# Peripheral.net
KiCad netlist of a schematic drawn in Altium Designer
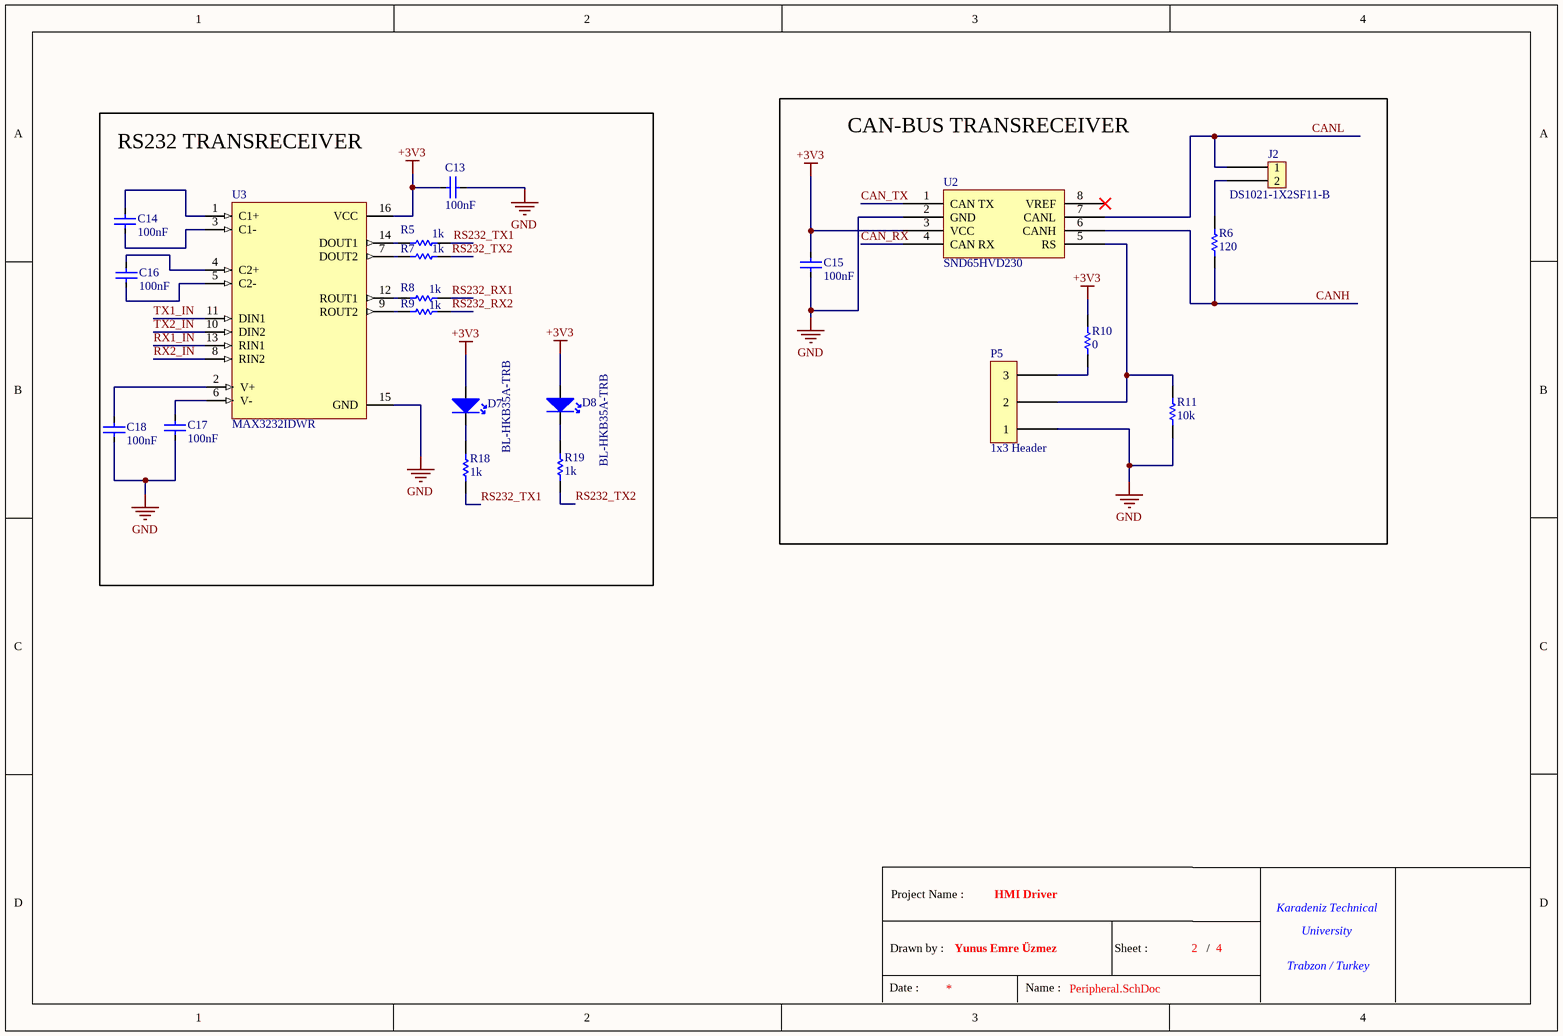
[diagram p0: Peripheral.SchDoc]

(export (version "E")
  (design (tool "Eeschema 10.0.6"))
  (components
    (comp (ref "C13")
      (value "100nF")
      (footprint "CAP-0603")
      (fields
        (field (name "MANUFACTURER") "TDK")
        (field (name "VOLTAGE") "50V")
        (field (name "TOLERANCE") "%10")
      )
      (libsource (lib "Motor_Driver") (part "CGA3E2X7R1H104K080AA"))
    )
    (comp (ref "C14")
      (value "100nF")
      (footprint "CAP-0603")
      (fields
        (field (name "MANUFACTURER") "TDK")
        (field (name "VOLTAGE") "50V")
        (field (name "TOLERANCE") "%10")
      )
      (libsource (lib "Motor_Driver") (part "CGA3E2X7R1H104K080AA"))
    )
    (comp (ref "C15")
      (value "100nF")
      (footprint "CAP-0603")
      (fields
        (field (name "MANUFACTURER") "TDK")
        (field (name "VOLTAGE") "50V")
        (field (name "TOLERANCE") "%10")
      )
      (libsource (lib "Motor_Driver") (part "CGA3E2X7R1H104K080AA"))
    )
    (comp (ref "C16")
      (value "100nF")
      (footprint "CAP-0603")
      (fields
        (field (name "MANUFACTURER") "TDK")
        (field (name "VOLTAGE") "50V")
        (field (name "TOLERANCE") "%10")
      )
      (libsource (lib "Motor_Driver") (part "CGA3E2X7R1H104K080AA"))
    )
    (comp (ref "C17")
      (value "100nF")
      (footprint "CAP-0603")
      (fields
        (field (name "MANUFACTURER") "TDK")
        (field (name "VOLTAGE") "50V")
        (field (name "TOLERANCE") "%10")
      )
      (libsource (lib "Motor_Driver") (part "CGA3E2X7R1H104K080AA"))
    )
    (comp (ref "C18")
      (value "100nF")
      (footprint "CAP-0603")
      (fields
        (field (name "MANUFACTURER") "TDK")
        (field (name "VOLTAGE") "50V")
        (field (name "TOLERANCE") "%10")
      )
      (libsource (lib "Motor_Driver") (part "CGA3E2X7R1H104K080AA"))
    )
    (comp (ref "D7")
      (value "BL-HKB35A-TRB")
      (footprint "LED-0805")
      (fields (field (name "MANUFACTURER") "BRIGHT LED"))
      (libsource (lib "Motor_Driver") (part "BL-HKB35A-TRB"))
    )
    (comp (ref "D8")
      (value "BL-HKB35A-TRB")
      (footprint "LED-0805")
      (fields (field (name "MANUFACTURER") "BRIGHT LED"))
      (libsource (lib "Motor_Driver") (part "BL-HKB35A-TRB"))
    )
    (comp (ref "J2")
      (value "DS1021-1X2SF11-B")
      (footprint "1x2 HEADER")
      (fields (field (name "MANUFACTURER") "KLS Electronic"))
      (libsource (lib "jl_lib") (part "DS1021-1X2SF11-B"))
    )
    (comp (ref "P5")
      (value "1x3 Header")
      (footprint "1x3 Header (2.54 mm)")
      (libsource (lib "LoRatoUSB") (part "1x3 Header"))
    )
    (comp (ref "R5")
      (value "1k")
      (footprint "Motor_Driver:RES-0603")
      (fields
        (field (name "MANUFACTURER") "Vishay")
        (field (name "TOLERANCE") "%1")
        (field (name "POWER") "0.1W")
      )
      (libsource (lib "My_Libs") (part "CRCW06031K00FKEAC"))
    )
    (comp (ref "R6")
      (value "120")
      (footprint "RES-0603")
      (fields
        (field (name "MANUFACTURER") "YAGEO")
        (field (name "TOLERANCE") "%1")
        (field (name "VOLTAGE") "75V")
      )
      (libsource (lib "jl_lib") (part "RC0603FR-07120RL"))
    )
    (comp (ref "R7")
      (value "1k")
      (footprint "Motor_Driver:RES-0603")
      (fields
        (field (name "MANUFACTURER") "Vishay")
        (field (name "TOLERANCE") "%1")
        (field (name "POWER") "0.1W")
      )
      (libsource (lib "My_Libs") (part "CRCW06031K00FKEAC"))
    )
    (comp (ref "R8")
      (value "1k")
      (footprint "Motor_Driver:RES-0603")
      (fields
        (field (name "MANUFACTURER") "Vishay")
        (field (name "TOLERANCE") "%1")
        (field (name "POWER") "0.1W")
      )
      (libsource (lib "My_Libs") (part "CRCW06031K00FKEAC"))
    )
    (comp (ref "R9")
      (value "1k")
      (footprint "Motor_Driver:RES-0603")
      (fields
        (field (name "MANUFACTURER") "Vishay")
        (field (name "TOLERANCE") "%1")
        (field (name "POWER") "0.1W")
      )
      (libsource (lib "My_Libs") (part "CRCW06031K00FKEAC"))
    )
    (comp (ref "R10")
      (value "0")
      (footprint "RES-0603")
      (fields
        (field (name "TOLERANCE") "%5")
        (field (name "MANUFACTURER") "ROYALOHM")
        (field (name "VOLTAGE") "75V")
      )
      (libsource (lib "jl_lib") (part "0603SAJ0000T5E"))
    )
    (comp (ref "R11")
      (value "10k")
      (footprint "Motor_Driver:RES-0603")
      (fields
        (field (name "MANUFACTURER") "Vishay")
        (field (name "TOLERANCE") "%1")
        (field (name "POWER") "0.1W")
      )
      (libsource (lib "My_Libs") (part "CRCW060310K0FKEA"))
    )
    (comp (ref "R18")
      (value "1k")
      (footprint "Motor_Driver:RES-0603")
      (fields
        (field (name "MANUFACTURER") "Vishay")
        (field (name "TOLERANCE") "%1")
        (field (name "POWER") "0.1W")
      )
      (libsource (lib "My_Libs") (part "CRCW06031K00FKEAC"))
    )
    (comp (ref "R19")
      (value "1k")
      (footprint "Motor_Driver:RES-0603")
      (fields
        (field (name "MANUFACTURER") "Vishay")
        (field (name "TOLERANCE") "%1")
        (field (name "POWER") "0.1W")
      )
      (libsource (lib "My_Libs") (part "CRCW06031K00FKEAC"))
    )
    (comp (ref "U2")
      (value "SND65HVD230")
      (footprint "SOIC-8")
      (fields (field (name "MANUFACTURER") "TI"))
      (libsource (lib "jl_lib") (part "SND65HVD230"))
    )
    (comp (ref "U3")
      (value "MAX3232IDWR")
      (footprint "SOIC-16")
      (fields (field (name "MANUFACTURER") "Texas"))
      (libsource (lib "jl_lib") (part "MAX3232IDWR"))
    )
  )
  (nets
    (net (code "1") (name "+3V3") (class "Default")
      (node (ref "C13") (pin "2") (pinfunction "2_2") (pintype "passive"))
      (node (ref "C15") (pin "1") (pinfunction "1_1") (pintype "passive"))
      (node (ref "D7") (pin "1") (pinfunction "A_1") (pintype "passive"))
      (node (ref "D8") (pin "1") (pinfunction "A_1") (pintype "passive"))
      (node (ref "R10") (pin "2") (pinfunction "2_2") (pintype "passive"))
      (node (ref "U2") (pin "3") (pinfunction "VCC_3") (pintype "passive"))
      (node (ref "U3") (pin "16") (pinfunction "VCC_16") (pintype "power_in"))
    )
    (net (code "2") (name "/CANH") (class "Default")
      (node (ref "R6") (pin "2") (pinfunction "2_2") (pintype "passive"))
      (node (ref "U2") (pin "6") (pinfunction "CANH_6") (pintype "passive"))
    )
    (net (code "3") (name "/CANL") (class "Default")
      (node (ref "J2") (pin "1") (pinfunction "1_1") (pintype "passive"))
      (node (ref "U2") (pin "7") (pinfunction "CANL_7") (pintype "passive"))
    )
    (net (code "4") (name "/CAN_RX") (class "Default")
      (node (ref "U2") (pin "4") (pinfunction "CAN_RX_4") (pintype "passive"))
    )
    (net (code "5") (name "/CAN_TX") (class "Default")
      (node (ref "U2") (pin "1") (pinfunction "CAN_TX_1") (pintype "passive"))
    )
    (net (code "6") (name "/RS232_RX1") (class "Default")
      (node (ref "R8") (pin "1") (pinfunction "1_1") (pintype "passive"))
    )
    (net (code "7") (name "/RS232_RX2") (class "Default")
      (node (ref "R9") (pin "1") (pinfunction "1_1") (pintype "passive"))
    )
    (net (code "8") (name "/RS232_TX1") (class "Default")
      (node (ref "R18") (pin "2") (pinfunction "2_2") (pintype "passive"))
      (node (ref "R5") (pin "1") (pinfunction "1_1") (pintype "passive"))
    )
    (net (code "9") (name "/RS232_TX2") (class "Default")
      (node (ref "R19") (pin "2") (pinfunction "2_2") (pintype "passive"))
      (node (ref "R7") (pin "1") (pinfunction "1_1") (pintype "passive"))
    )
    (net (code "10") (name "/RX1_IN") (class "Default")
      (node (ref "U3") (pin "13") (pinfunction "RIN1_13") (pintype "input"))
    )
    (net (code "11") (name "/RX2_IN") (class "Default")
      (node (ref "U3") (pin "8") (pinfunction "RIN2_8") (pintype "input"))
    )
    (net (code "12") (name "/TX1_IN") (class "Default")
      (node (ref "U3") (pin "11") (pinfunction "DIN1_11") (pintype "input"))
    )
    (net (code "13") (name "/TX2_IN") (class "Default")
      (node (ref "U3") (pin "10") (pinfunction "DIN2_10") (pintype "input"))
    )
    (net (code "14") (name "GND") (class "Default")
      (node (ref "C13") (pin "1") (pinfunction "1_1") (pintype "passive"))
      (node (ref "C15") (pin "2") (pinfunction "2_2") (pintype "passive"))
      (node (ref "C17") (pin "2") (pinfunction "2_2") (pintype "passive"))
      (node (ref "C18") (pin "2") (pinfunction "2_2") (pintype "passive"))
      (node (ref "P5") (pin "1") (pinfunction "1_1") (pintype "passive"))
      (node (ref "R11") (pin "1") (pinfunction "1_1") (pintype "passive"))
      (node (ref "U2") (pin "2") (pinfunction "GND_2") (pintype "passive"))
      (node (ref "U3") (pin "15") (pinfunction "GND_15") (pintype "power_in"))
    )
    (net (code "15") (name "Net-(D7-K)") (class "Default")
      (node (ref "D7") (pin "2") (pinfunction "K_2") (pintype "passive"))
      (node (ref "R18") (pin "1") (pinfunction "1_1") (pintype "passive"))
    )
    (net (code "16") (name "Net-(D8-K)") (class "Default")
      (node (ref "D8") (pin "2") (pinfunction "K_2") (pintype "passive"))
      (node (ref "R19") (pin "1") (pinfunction "1_1") (pintype "passive"))
    )
    (net (code "17") (name "Net-(J2-Pad2)") (class "Default")
      (node (ref "J2") (pin "2") (pinfunction "2_2") (pintype "passive"))
      (node (ref "R6") (pin "1") (pinfunction "1_1") (pintype "passive"))
    )
    (net (code "18") (name "Net-(P5-Pad3)") (class "Default")
      (node (ref "P5") (pin "3") (pinfunction "3_3") (pintype "passive"))
      (node (ref "R10") (pin "1") (pinfunction "1_1") (pintype "passive"))
    )
    (net (code "19") (name "Net-(U2-RS)") (class "Default")
      (node (ref "P5") (pin "2") (pinfunction "2_2") (pintype "passive"))
      (node (ref "R11") (pin "2") (pinfunction "2_2") (pintype "passive"))
      (node (ref "U2") (pin "5") (pinfunction "RS_5") (pintype "passive"))
    )
    (net (code "20") (name "Net-(U3-C1+)") (class "Default")
      (node (ref "C14") (pin "1") (pinfunction "1_1") (pintype "passive"))
      (node (ref "U3") (pin "1") (pinfunction "C1+_1") (pintype "input"))
    )
    (net (code "21") (name "Net-(U3-C1-)") (class "Default")
      (node (ref "C14") (pin "2") (pinfunction "2_2") (pintype "passive"))
      (node (ref "U3") (pin "3") (pinfunction "C1-_3") (pintype "input"))
    )
    (net (code "22") (name "Net-(U3-C2+)") (class "Default")
      (node (ref "C16") (pin "1") (pinfunction "1_1") (pintype "passive"))
      (node (ref "U3") (pin "4") (pinfunction "C2+_4") (pintype "input"))
    )
    (net (code "23") (name "Net-(U3-C2-)") (class "Default")
      (node (ref "C16") (pin "2") (pinfunction "2_2") (pintype "passive"))
      (node (ref "U3") (pin "5") (pinfunction "C2-_5") (pintype "input"))
    )
    (net (code "24") (name "Net-(U3-DOUT1)") (class "Default")
      (node (ref "R5") (pin "2") (pinfunction "2_2") (pintype "passive"))
      (node (ref "U3") (pin "14") (pinfunction "DOUT1_14") (pintype "output"))
    )
    (net (code "25") (name "Net-(U3-DOUT2)") (class "Default")
      (node (ref "R7") (pin "2") (pinfunction "2_2") (pintype "passive"))
      (node (ref "U3") (pin "7") (pinfunction "DOUT2_7") (pintype "output"))
    )
    (net (code "26") (name "Net-(U3-ROUT1)") (class "Default")
      (node (ref "R8") (pin "2") (pinfunction "2_2") (pintype "passive"))
      (node (ref "U3") (pin "12") (pinfunction "ROUT1_12") (pintype "output"))
    )
    (net (code "27") (name "Net-(U3-ROUT2)") (class "Default")
      (node (ref "R9") (pin "2") (pinfunction "2_2") (pintype "passive"))
      (node (ref "U3") (pin "9") (pinfunction "ROUT2_9") (pintype "output"))
    )
    (net (code "28") (name "Net-(U3-V+)") (class "Default")
      (node (ref "C18") (pin "1") (pinfunction "1_1") (pintype "passive"))
      (node (ref "U3") (pin "2") (pinfunction "V+_2") (pintype "input"))
    )
    (net (code "29") (name "Net-(U3-V-)") (class "Default")
      (node (ref "C17") (pin "1") (pinfunction "1_1") (pintype "passive"))
      (node (ref "U3") (pin "6") (pinfunction "V-_6") (pintype "input"))
    )
    (net (code "30") (name "unconnected-(U2-VREF-Pad8)") (class "Default")
      (node (ref "U2") (pin "8") (pinfunction "VREF_8") (pintype "passive+no_connect"))
    )
  )
)
